# RFDIO.net
KiCad netlist of a schematic drawn in Altium Designer
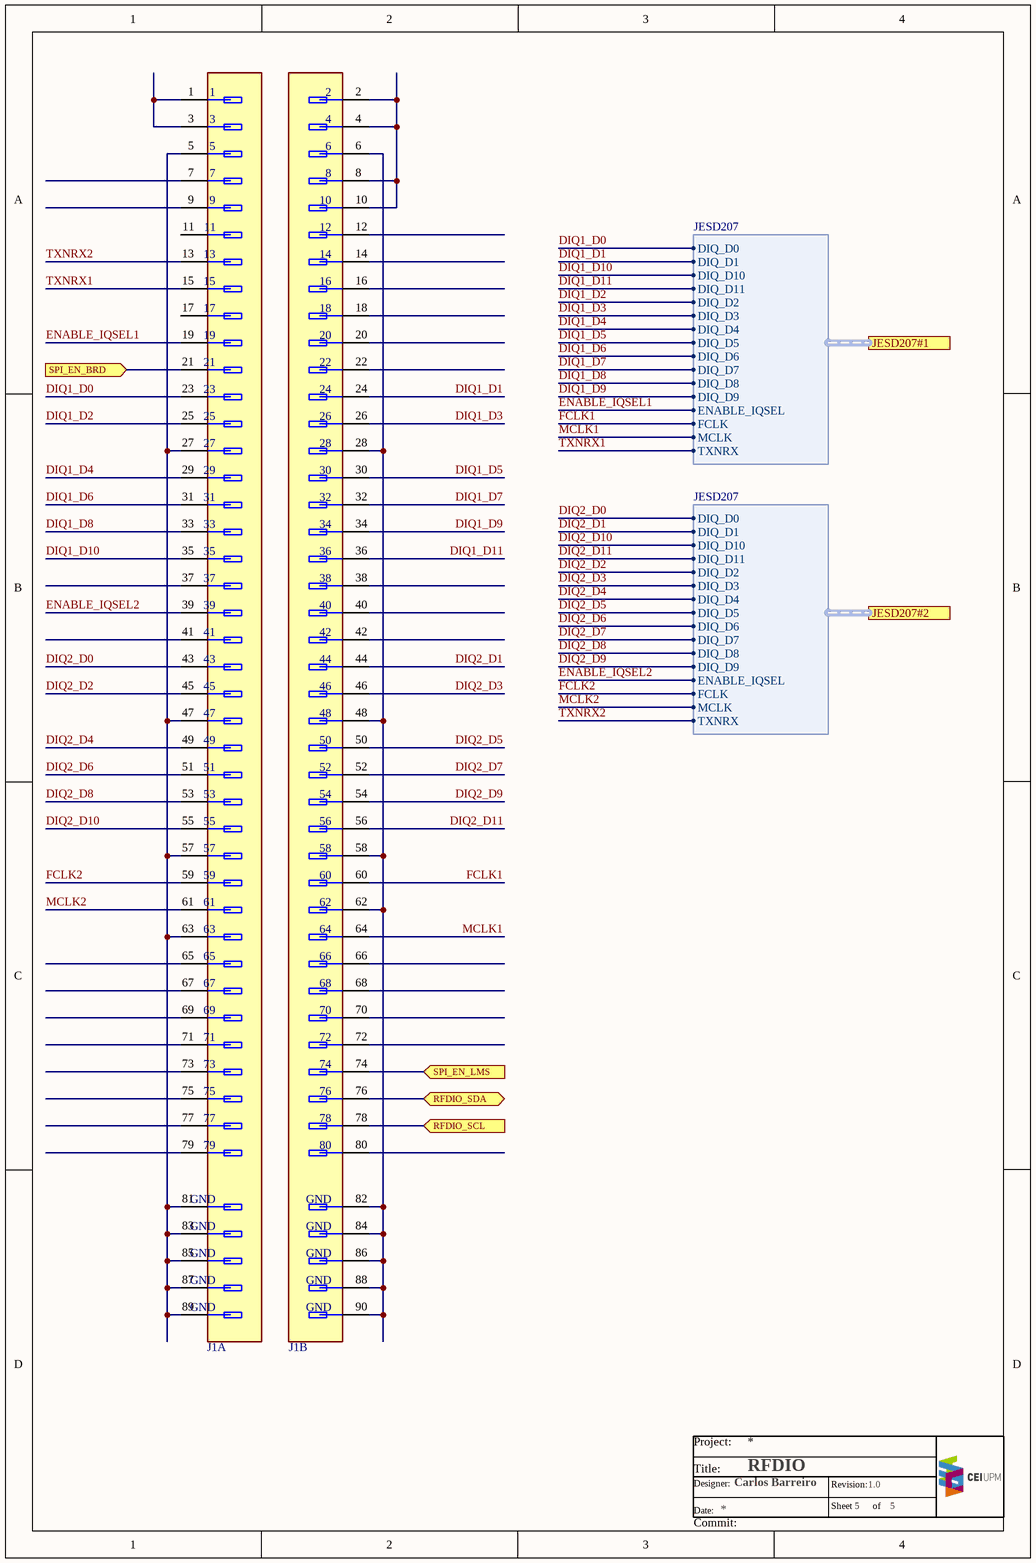
[diagram p0: RFDIO.SchDoc]

(export (version "E")
  (design (tool "Eeschema 10.0.6"))
  (components
    (comp (ref "J1")
      (value "FX10A-80S/8-SV")
      (footprint "HRS_FX10A-80S/8-SV")
      (description "80 Position Connector Header, Outer Shroud Contacts Surface Mount Gold")
      (libsource (lib "SpaceVNXBaseBoard") (part "FX10A-80S/8-SV"))
    )
  )
  (nets
    (net (code "2") (name "/DIQ1_D0") (class "Default")
      (node (ref "J1") (pin "23") (pinfunction "23_23") (pintype "passive"))
    )
    (net (code "3") (name "/DIQ1_D1") (class "Default")
      (node (ref "J1") (pin "24") (pinfunction "24_24") (pintype "passive"))
    )
    (net (code "4") (name "/DIQ1_D2") (class "Default")
      (node (ref "J1") (pin "25") (pinfunction "25_25") (pintype "passive"))
    )
    (net (code "5") (name "/DIQ1_D3") (class "Default")
      (node (ref "J1") (pin "26") (pinfunction "26_26") (pintype "passive"))
    )
    (net (code "6") (name "/DIQ1_D4") (class "Default")
      (node (ref "J1") (pin "29") (pinfunction "29_29") (pintype "passive"))
    )
    (net (code "7") (name "/DIQ1_D5") (class "Default")
      (node (ref "J1") (pin "30") (pinfunction "30_30") (pintype "passive"))
    )
    (net (code "8") (name "/DIQ1_D6") (class "Default")
      (node (ref "J1") (pin "31") (pinfunction "31_31") (pintype "passive"))
    )
    (net (code "9") (name "/DIQ1_D7") (class "Default")
      (node (ref "J1") (pin "32") (pinfunction "32_32") (pintype "passive"))
    )
    (net (code "10") (name "/DIQ1_D8") (class "Default")
      (node (ref "J1") (pin "33") (pinfunction "33_33") (pintype "passive"))
    )
    (net (code "11") (name "/DIQ1_D9") (class "Default")
      (node (ref "J1") (pin "34") (pinfunction "34_34") (pintype "passive"))
    )
    (net (code "12") (name "/DIQ1_D10") (class "Default")
      (node (ref "J1") (pin "35") (pinfunction "35_35") (pintype "passive"))
    )
    (net (code "13") (name "/DIQ1_D11") (class "Default")
      (node (ref "J1") (pin "36") (pinfunction "36_36") (pintype "passive"))
    )
    (net (code "14") (name "/DIQ2_D0") (class "Default")
      (node (ref "J1") (pin "43") (pinfunction "43_43") (pintype "passive"))
    )
    (net (code "15") (name "/DIQ2_D1") (class "Default")
      (node (ref "J1") (pin "44") (pinfunction "44_44") (pintype "passive"))
    )
    (net (code "16") (name "/DIQ2_D2") (class "Default")
      (node (ref "J1") (pin "45") (pinfunction "45_45") (pintype "passive"))
    )
    (net (code "17") (name "/DIQ2_D3") (class "Default")
      (node (ref "J1") (pin "46") (pinfunction "46_46") (pintype "passive"))
    )
    (net (code "18") (name "/DIQ2_D4") (class "Default")
      (node (ref "J1") (pin "49") (pinfunction "49_49") (pintype "passive"))
    )
    (net (code "19") (name "/DIQ2_D5") (class "Default")
      (node (ref "J1") (pin "50") (pinfunction "50_50") (pintype "passive"))
    )
    (net (code "20") (name "/DIQ2_D6") (class "Default")
      (node (ref "J1") (pin "51") (pinfunction "51_51") (pintype "passive"))
    )
    (net (code "21") (name "/DIQ2_D7") (class "Default")
      (node (ref "J1") (pin "52") (pinfunction "52_52") (pintype "passive"))
    )
    (net (code "22") (name "/DIQ2_D8") (class "Default")
      (node (ref "J1") (pin "53") (pinfunction "53_53") (pintype "passive"))
    )
    (net (code "23") (name "/DIQ2_D9") (class "Default")
      (node (ref "J1") (pin "54") (pinfunction "54_54") (pintype "passive"))
    )
    (net (code "24") (name "/DIQ2_D10") (class "Default")
      (node (ref "J1") (pin "55") (pinfunction "55_55") (pintype "passive"))
    )
    (net (code "25") (name "/DIQ2_D11") (class "Default")
      (node (ref "J1") (pin "56") (pinfunction "56_56") (pintype "passive"))
    )
    (net (code "26") (name "/ENABLE_IQSEL1") (class "Default")
      (node (ref "J1") (pin "19") (pinfunction "19_19") (pintype "passive"))
    )
    (net (code "27") (name "/ENABLE_IQSEL2") (class "Default")
      (node (ref "J1") (pin "39") (pinfunction "39_39") (pintype "passive"))
    )
    (net (code "28") (name "/FCLK1") (class "Default")
      (node (ref "J1") (pin "60") (pinfunction "60_60") (pintype "passive"))
    )
    (net (code "29") (name "/FCLK2") (class "Default")
      (node (ref "J1") (pin "59") (pinfunction "59_59") (pintype "passive"))
    )
    (net (code "30") (name "/MCLK1") (class "Default")
      (node (ref "J1") (pin "64") (pinfunction "64_64") (pintype "passive"))
    )
    (net (code "31") (name "/MCLK2") (class "Default")
      (node (ref "J1") (pin "61") (pinfunction "61_61") (pintype "passive"))
    )
    (net (code "32") (name "/RFDIO_SCL") (class "Default")
      (node (ref "J1") (pin "78") (pinfunction "78_78") (pintype "passive"))
    )
    (net (code "33") (name "/RFDIO_SDA") (class "Default")
      (node (ref "J1") (pin "76") (pinfunction "76_76") (pintype "passive"))
    )
    (net (code "34") (name "/SPI_EN_BRD") (class "Default")
      (node (ref "J1") (pin "21") (pinfunction "21_21") (pintype "passive"))
    )
    (net (code "35") (name "/SPI_EN_LMS") (class "Default")
      (node (ref "J1") (pin "74") (pinfunction "74_74") (pintype "passive"))
    )
    (net (code "36") (name "/TXNRX1") (class "Default")
      (node (ref "J1") (pin "15") (pinfunction "15_15") (pintype "passive"))
    )
    (net (code "37") (name "/TXNRX2") (class "Default")
      (node (ref "J1") (pin "13") (pinfunction "13_13") (pintype "passive"))
    )
    (net (code "39") (name "Net-(J1-Pad1)") (class "Default")
      (node (ref "J1") (pin "1") (pinfunction "1_1") (pintype "passive"))
      (node (ref "J1") (pin "3") (pinfunction "3_3") (pintype "passive"))
    )
    (net (code "40") (name "Net-(J1-Pad10)") (class "Default")
      (node (ref "J1") (pin "10") (pinfunction "10_10") (pintype "passive"))
      (node (ref "J1") (pin "2") (pinfunction "2_2") (pintype "passive"))
      (node (ref "J1") (pin "4") (pinfunction "4_4") (pintype "passive"))
      (node (ref "J1") (pin "8") (pinfunction "8_8") (pintype "passive"))
    )
    (net (code "41") (name "Net-(J1-Pad27)") (class "Default")
      (node (ref "J1") (pin "27") (pinfunction "27_27") (pintype "passive"))
      (node (ref "J1") (pin "47") (pinfunction "47_47") (pintype "passive"))
      (node (ref "J1") (pin "5") (pinfunction "5_5") (pintype "passive"))
      (node (ref "J1") (pin "57") (pinfunction "57_57") (pintype "passive"))
      (node (ref "J1") (pin "63") (pinfunction "63_63") (pintype "passive"))
      (node (ref "J1") (pin "81") (pinfunction "GND_81") (pintype "passive"))
      (node (ref "J1") (pin "83") (pinfunction "GND_83") (pintype "passive"))
      (node (ref "J1") (pin "85") (pinfunction "GND_85") (pintype "passive"))
      (node (ref "J1") (pin "87") (pinfunction "GND_87") (pintype "passive"))
      (node (ref "J1") (pin "89") (pinfunction "GND_89") (pintype "passive"))
    )
    (net (code "42") (name "Net-(J1-Pad28)") (class "Default")
      (node (ref "J1") (pin "28") (pinfunction "28_28") (pintype "passive"))
      (node (ref "J1") (pin "48") (pinfunction "48_48") (pintype "passive"))
      (node (ref "J1") (pin "58") (pinfunction "58_58") (pintype "passive"))
      (node (ref "J1") (pin "6") (pinfunction "6_6") (pintype "passive"))
      (node (ref "J1") (pin "62") (pinfunction "62_62") (pintype "passive"))
      (node (ref "J1") (pin "82") (pinfunction "GND_82") (pintype "passive"))
      (node (ref "J1") (pin "84") (pinfunction "GND_84") (pintype "passive"))
      (node (ref "J1") (pin "86") (pinfunction "GND_86") (pintype "passive"))
      (node (ref "J1") (pin "88") (pinfunction "GND_88") (pintype "passive"))
      (node (ref "J1") (pin "90") (pinfunction "GND_90") (pintype "passive"))
    )
    (net (code "43") (name "unconnected-(J1-Pad7)") (class "Default")
      (node (ref "J1") (pin "7") (pinfunction "7_7") (pintype "passive"))
    )
    (net (code "44") (name "unconnected-(J1-Pad9)") (class "Default")
      (node (ref "J1") (pin "9") (pinfunction "9_9") (pintype "passive"))
    )
    (net (code "45") (name "unconnected-(J1-Pad11)") (class "Default")
      (node (ref "J1") (pin "11") (pinfunction "11_11") (pintype "passive"))
    )
    (net (code "46") (name "unconnected-(J1-Pad12)") (class "Default")
      (node (ref "J1") (pin "12") (pinfunction "12_12") (pintype "passive"))
    )
    (net (code "47") (name "unconnected-(J1-Pad14)") (class "Default")
      (node (ref "J1") (pin "14") (pinfunction "14_14") (pintype "passive"))
    )
    (net (code "48") (name "unconnected-(J1-Pad16)") (class "Default")
      (node (ref "J1") (pin "16") (pinfunction "16_16") (pintype "passive"))
    )
    (net (code "49") (name "unconnected-(J1-Pad17)") (class "Default")
      (node (ref "J1") (pin "17") (pinfunction "17_17") (pintype "passive"))
    )
    (net (code "50") (name "unconnected-(J1-Pad18)") (class "Default")
      (node (ref "J1") (pin "18") (pinfunction "18_18") (pintype "passive"))
    )
    (net (code "51") (name "unconnected-(J1-Pad20)") (class "Default")
      (node (ref "J1") (pin "20") (pinfunction "20_20") (pintype "passive"))
    )
    (net (code "52") (name "unconnected-(J1-Pad22)") (class "Default")
      (node (ref "J1") (pin "22") (pinfunction "22_22") (pintype "passive"))
    )
    (net (code "53") (name "unconnected-(J1-Pad37)") (class "Default")
      (node (ref "J1") (pin "37") (pinfunction "37_37") (pintype "passive"))
    )
    (net (code "54") (name "unconnected-(J1-Pad38)") (class "Default")
      (node (ref "J1") (pin "38") (pinfunction "38_38") (pintype "passive"))
    )
    (net (code "55") (name "unconnected-(J1-Pad40)") (class "Default")
      (node (ref "J1") (pin "40") (pinfunction "40_40") (pintype "passive"))
    )
    (net (code "56") (name "unconnected-(J1-Pad41)") (class "Default")
      (node (ref "J1") (pin "41") (pinfunction "41_41") (pintype "passive"))
    )
    (net (code "57") (name "unconnected-(J1-Pad42)") (class "Default")
      (node (ref "J1") (pin "42") (pinfunction "42_42") (pintype "passive"))
    )
    (net (code "58") (name "unconnected-(J1-Pad65)") (class "Default")
      (node (ref "J1") (pin "65") (pinfunction "65_65") (pintype "passive"))
    )
    (net (code "59") (name "unconnected-(J1-Pad66)") (class "Default")
      (node (ref "J1") (pin "66") (pinfunction "66_66") (pintype "passive"))
    )
    (net (code "60") (name "unconnected-(J1-Pad67)") (class "Default")
      (node (ref "J1") (pin "67") (pinfunction "67_67") (pintype "passive"))
    )
    (net (code "61") (name "unconnected-(J1-Pad68)") (class "Default")
      (node (ref "J1") (pin "68") (pinfunction "68_68") (pintype "passive"))
    )
    (net (code "62") (name "unconnected-(J1-Pad69)") (class "Default")
      (node (ref "J1") (pin "69") (pinfunction "69_69") (pintype "passive"))
    )
    (net (code "63") (name "unconnected-(J1-Pad70)") (class "Default")
      (node (ref "J1") (pin "70") (pinfunction "70_70") (pintype "passive"))
    )
    (net (code "64") (name "unconnected-(J1-Pad71)") (class "Default")
      (node (ref "J1") (pin "71") (pinfunction "71_71") (pintype "passive"))
    )
    (net (code "65") (name "unconnected-(J1-Pad72)") (class "Default")
      (node (ref "J1") (pin "72") (pinfunction "72_72") (pintype "passive"))
    )
    (net (code "66") (name "unconnected-(J1-Pad73)") (class "Default")
      (node (ref "J1") (pin "73") (pinfunction "73_73") (pintype "passive"))
    )
    (net (code "67") (name "unconnected-(J1-Pad75)") (class "Default")
      (node (ref "J1") (pin "75") (pinfunction "75_75") (pintype "passive"))
    )
    (net (code "68") (name "unconnected-(J1-Pad77)") (class "Default")
      (node (ref "J1") (pin "77") (pinfunction "77_77") (pintype "passive"))
    )
    (net (code "69") (name "unconnected-(J1-Pad79)") (class "Default")
      (node (ref "J1") (pin "79") (pinfunction "79_79") (pintype "passive"))
    )
    (net (code "70") (name "unconnected-(J1-Pad80)") (class "Default")
      (node (ref "J1") (pin "80") (pinfunction "80_80") (pintype "passive"))
    )
  )
)
